# Battery1.net
KiCad netlist of a schematic drawn in Altium Designer
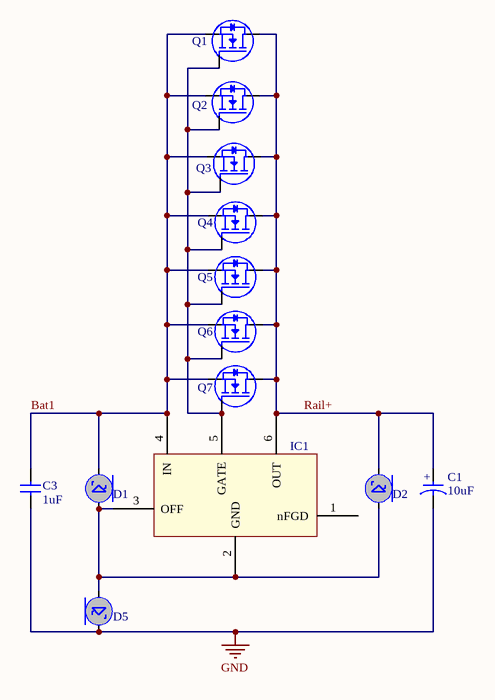
[diagram p0: Battery1.SchDoc]

(export (version "E")
  (design (tool "Eeschema 10.0.6"))
  (components
    (comp (ref "C1")
      (value "10uF")
      (footprint "CAP22uF100V")
      (fields (field (name "Comment") "CapPol"))
      (libsource (lib "SubjuGator8") (part "CapPol"))
    )
    (comp (ref "C3")
      (value "1uF")
      (footprint "CAPC1206")
      (fields (field (name "Comment") "Cap"))
      (libsource (lib "SubjuGator8") (part "Cap"))
    )
    (comp (ref "D1")
      (value "Schottky")
      (footprint "SS110-TP")
      (description "Schottky Diode Template")
      (libsource (lib "SubjuGator8") (part "Schottky"))
    )
    (comp (ref "D2")
      (value "SMBJ100A-13-F")
      (footprint "SMBJ100A-13-F")
      (description "TVS DIODE 100VWM 162VC SMB")
      (libsource (lib "SubjuGator8") (part "SMBJ100A-13-F"))
    )
    (comp (ref "D5")
      (value "Schottky")
      (footprint "SS110-TP")
      (description "Schottky Diode Template")
      (libsource (lib "") (part "Schottky_1"))
    )
    (comp (ref "IC1")
      (value "LM5050MK-2/NOPB")
      (footprint "LM5050MK-2/NOPB")
      (description "IC OR CTRLR N+1 6SOT")
      (libsource (lib "SubjuGator8") (part "LM5050MK-2/NOPB"))
    )
    (comp (ref "Q1")
      (value "CSD19502Q5B")
      (footprint "CSD19502Q5B")
      (description "NEXFET Power MOSFET")
      (libsource (lib "SubjuGator8") (part "CSD19502Q5B"))
    )
    (comp (ref "Q2")
      (value "CSD19502Q5B")
      (footprint "CSD19502Q5B")
      (description "NEXFET Power MOSFET")
      (libsource (lib "SubjuGator8") (part "CSD19502Q5B"))
    )
    (comp (ref "Q3")
      (value "CSD19502Q5B")
      (footprint "CSD19502Q5B")
      (description "NEXFET Power MOSFET")
      (libsource (lib "SubjuGator8") (part "CSD19502Q5B"))
    )
    (comp (ref "Q4")
      (value "CSD19502Q5B")
      (footprint "CSD19502Q5B")
      (description "NEXFET Power MOSFET")
      (libsource (lib "SubjuGator8") (part "CSD19502Q5B"))
    )
    (comp (ref "Q5")
      (value "CSD19502Q5B")
      (footprint "CSD19502Q5B")
      (description "NEXFET Power MOSFET")
      (libsource (lib "SubjuGator8") (part "CSD19502Q5B"))
    )
    (comp (ref "Q6")
      (value "CSD19502Q5B")
      (footprint "CSD19502Q5B")
      (description "NEXFET Power MOSFET")
      (libsource (lib "SubjuGator8") (part "CSD19502Q5B"))
    )
    (comp (ref "Q7")
      (value "CSD19502Q5B")
      (footprint "CSD19502Q5B")
      (description "NEXFET Power MOSFET")
      (libsource (lib "SubjuGator8") (part "CSD19502Q5B"))
    )
  )
  (nets
    (net (code "1") (name "/Bat1") (class "Default")
      (node (ref "C3") (pin "1") (pinfunction "A_1") (pintype "passive"))
      (node (ref "D1") (pin "C") (pinfunction "C_C") (pintype "passive"))
      (node (ref "IC1") (pin "4") (pinfunction "IN_4") (pintype "passive"))
      (node (ref "Q1") (pin "S") (pinfunction "S_S") (pintype "passive"))
      (node (ref "Q2") (pin "S") (pinfunction "S_S") (pintype "passive"))
      (node (ref "Q3") (pin "S") (pinfunction "S_S") (pintype "passive"))
      (node (ref "Q4") (pin "S") (pinfunction "S_S") (pintype "passive"))
      (node (ref "Q5") (pin "S") (pinfunction "S_S") (pintype "passive"))
      (node (ref "Q6") (pin "S") (pinfunction "S_S") (pintype "passive"))
      (node (ref "Q7") (pin "S") (pinfunction "S_S") (pintype "passive"))
    )
    (net (code "2") (name "/Rail+") (class "Default")
      (node (ref "C1") (pin "1") (pinfunction "A_1") (pintype "passive"))
      (node (ref "D2") (pin "C") (pinfunction "C_C") (pintype "passive"))
      (node (ref "IC1") (pin "6") (pinfunction "OUT_6") (pintype "passive"))
      (node (ref "Q1") (pin "D") (pinfunction "D_D") (pintype "passive"))
      (node (ref "Q2") (pin "D") (pinfunction "D_D") (pintype "passive"))
      (node (ref "Q3") (pin "D") (pinfunction "D_D") (pintype "passive"))
      (node (ref "Q4") (pin "D") (pinfunction "D_D") (pintype "passive"))
      (node (ref "Q5") (pin "D") (pinfunction "D_D") (pintype "passive"))
      (node (ref "Q6") (pin "D") (pinfunction "D_D") (pintype "passive"))
      (node (ref "Q7") (pin "D") (pinfunction "D_D") (pintype "passive"))
    )
    (net (code "3") (name "GND") (class "Default")
      (node (ref "C1") (pin "2") (pinfunction "B_2") (pintype "passive"))
      (node (ref "C3") (pin "2") (pinfunction "B_2") (pintype "passive"))
      (node (ref "D5") (pin "C") (pinfunction "C_C") (pintype "passive"))
    )
    (net (code "4") (name "Net-(IC1-GATE)") (class "Default")
      (node (ref "IC1") (pin "5") (pinfunction "GATE_5") (pintype "passive"))
      (node (ref "Q1") (pin "G") (pinfunction "G_G") (pintype "passive"))
      (node (ref "Q2") (pin "G") (pinfunction "G_G") (pintype "passive"))
      (node (ref "Q3") (pin "G") (pinfunction "G_G") (pintype "passive"))
      (node (ref "Q4") (pin "G") (pinfunction "G_G") (pintype "passive"))
      (node (ref "Q5") (pin "G") (pinfunction "G_G") (pintype "passive"))
      (node (ref "Q6") (pin "G") (pinfunction "G_G") (pintype "passive"))
      (node (ref "Q7") (pin "G") (pinfunction "G_G") (pintype "passive"))
    )
    (net (code "5") (name "Net-(IC1-GND)") (class "Default")
      (node (ref "D1") (pin "A") (pinfunction "A_A") (pintype "passive"))
      (node (ref "D2") (pin "A") (pinfunction "A_A") (pintype "passive"))
      (node (ref "D5") (pin "A") (pinfunction "A_A") (pintype "passive"))
      (node (ref "IC1") (pin "2") (pinfunction "GND_2") (pintype "passive"))
      (node (ref "IC1") (pin "3") (pinfunction "OFF_3") (pintype "passive"))
    )
    (net (code "6") (name "unconnected-(IC1-nFGD-Pad1)") (class "Default")
      (node (ref "IC1") (pin "1") (pinfunction "nFGD_1") (pintype "passive"))
    )
  )
)
